# ArcadeMachine.net
KiCad netlist of a schematic drawn in EAGLE
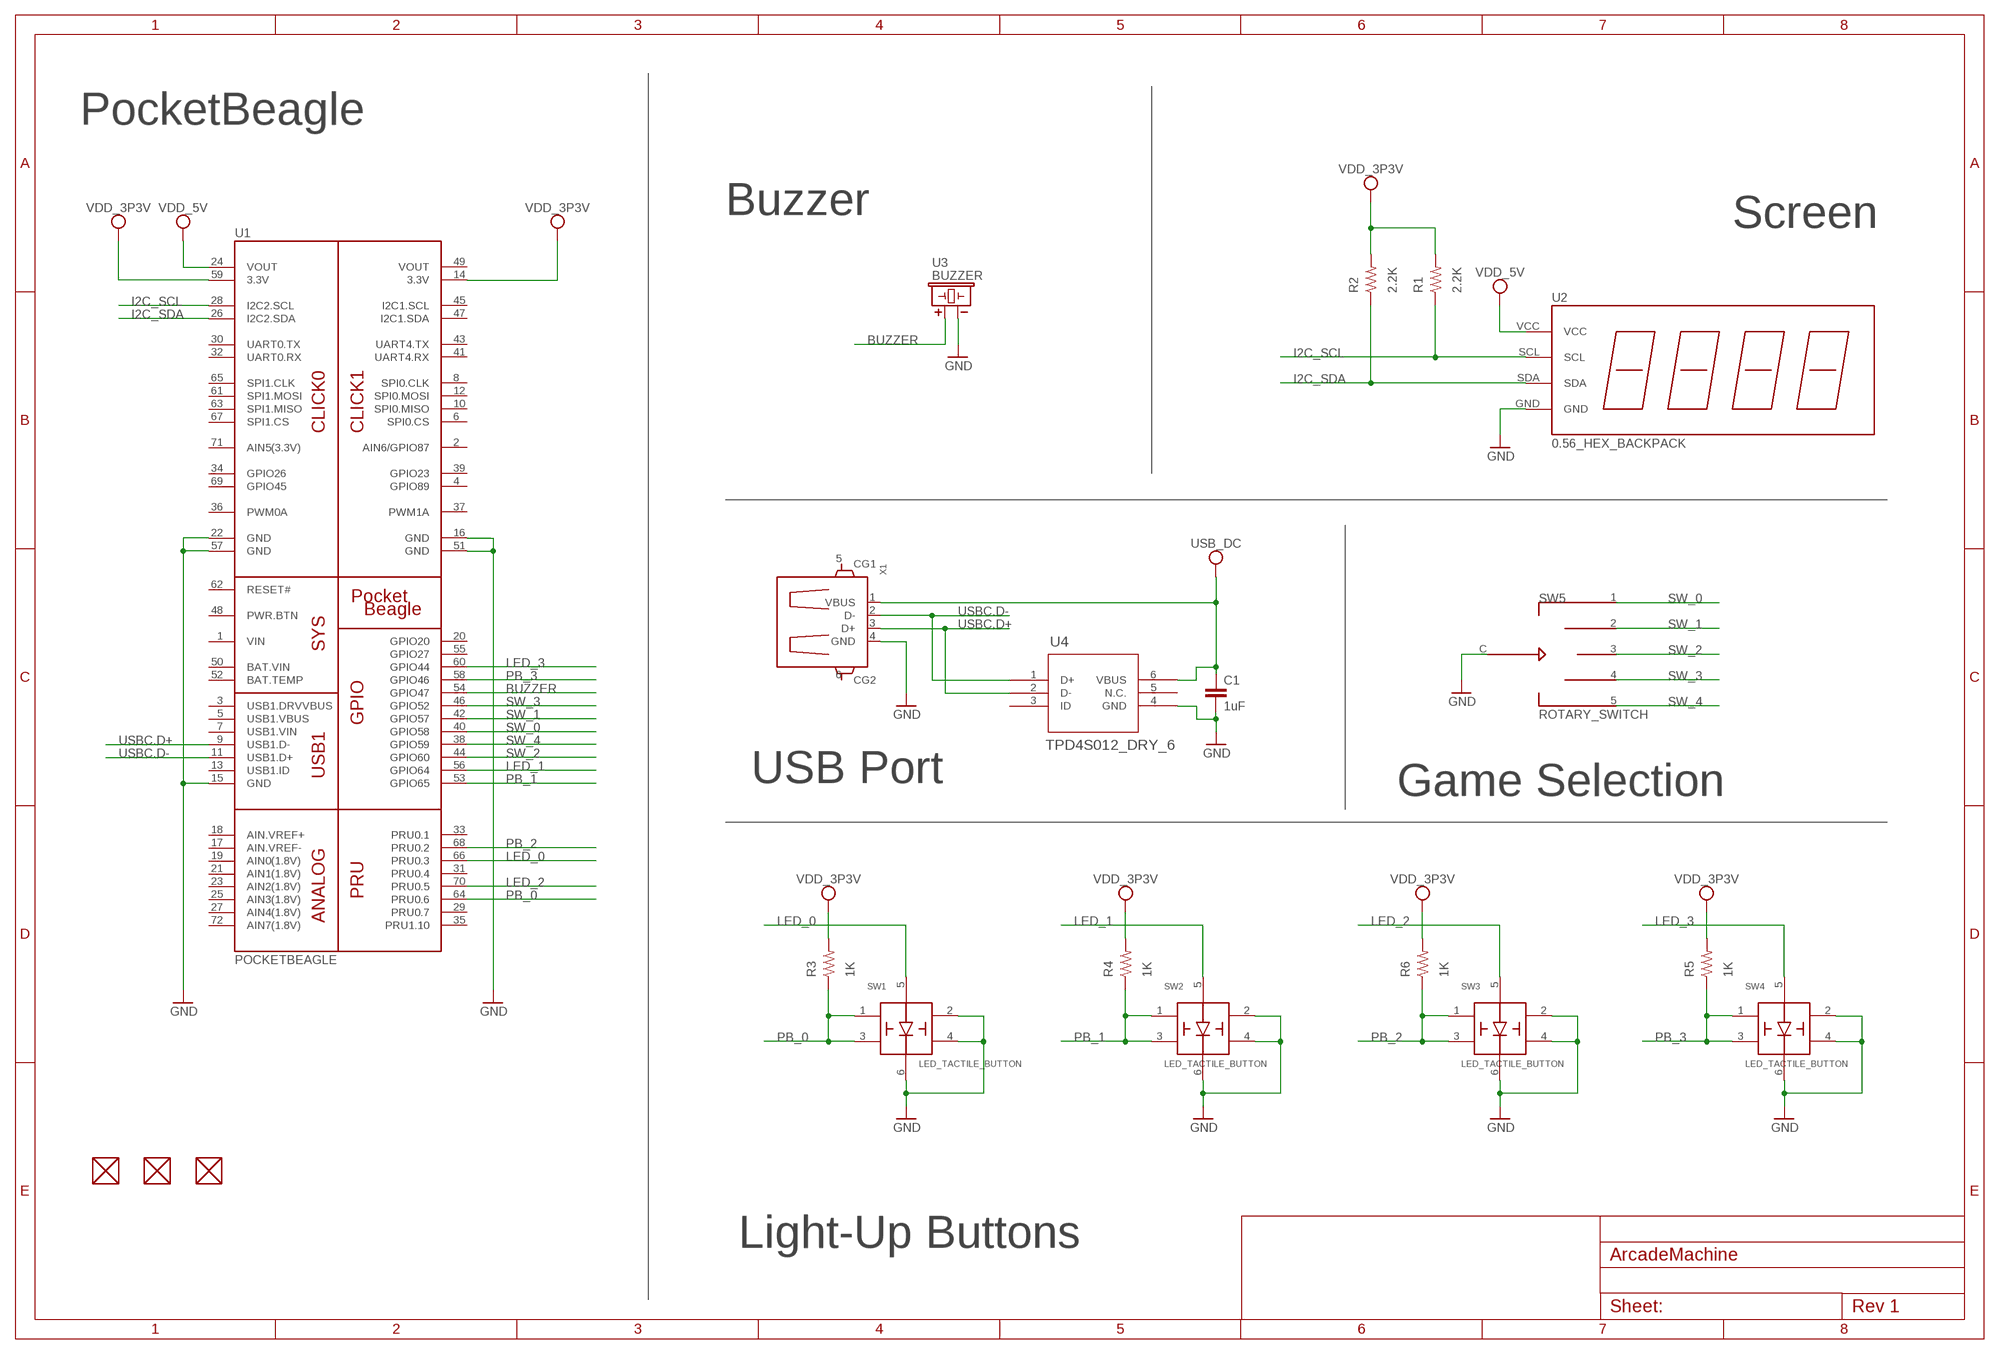
[diagram p0: schematic, sheet 1]

(export (version "E")
  (design (tool "Eeschema 10.0.6"))
  (components
    (comp (ref "C1")
      (value "1uF")
      (footprint "eagle-import:SPARKFUN-CAPACITORS_0603-CAP")
      (libsource (lib "eagle-import") (part "SPARKFUN-CAPACITORS_CAP0603-CAP"))
    )
    (comp (ref "FUD1")
      (value "FIDUCIAL")
      (footprint "eagle-import:FIDUCIAL_40MIL")
      (libsource (lib "eagle-import") (part "FIDUCIAL"))
    )
    (comp (ref "FUD2")
      (value "FIDUCIAL")
      (footprint "eagle-import:FIDUCIAL_40MIL")
      (libsource (lib "eagle-import") (part "FIDUCIAL"))
    )
    (comp (ref "FUD3")
      (value "FIDUCIAL")
      (footprint "eagle-import:FIDUCIAL_40MIL")
      (libsource (lib "eagle-import") (part "FIDUCIAL"))
    )
    (comp (ref "R1")
      (value "2.2K")
      (footprint "eagle-import:R0603")
      (libsource (lib "eagle-import") (part "ENGI301_R_R0603"))
    )
    (comp (ref "R2")
      (value "2.2K")
      (footprint "eagle-import:R0603")
      (libsource (lib "eagle-import") (part "ENGI301_R_R0603"))
    )
    (comp (ref "R3")
      (value "1K")
      (footprint "eagle-import:R0603")
      (libsource (lib "eagle-import") (part "R_R0603"))
    )
    (comp (ref "R4")
      (value "1K")
      (footprint "eagle-import:R0603")
      (libsource (lib "eagle-import") (part "R_R0603"))
    )
    (comp (ref "R5")
      (value "1K")
      (footprint "eagle-import:R0603")
      (libsource (lib "eagle-import") (part "R_R0603"))
    )
    (comp (ref "R6")
      (value "1K")
      (footprint "eagle-import:R0603")
      (libsource (lib "eagle-import") (part "R_R0603"))
    )
    (comp (ref "SW1")
      (value "LED_TACTILE_BUTTON")
      (footprint "eagle-import:LED_TACTILE_BUTTON")
      (libsource (lib "eagle-import") (part "LED_TACTILE_BUTTON"))
    )
    (comp (ref "SW2")
      (value "LED_TACTILE_BUTTON")
      (footprint "eagle-import:LED_TACTILE_BUTTON")
      (libsource (lib "eagle-import") (part "LED_TACTILE_BUTTON"))
    )
    (comp (ref "SW3")
      (value "LED_TACTILE_BUTTON")
      (footprint "eagle-import:LED_TACTILE_BUTTON")
      (libsource (lib "eagle-import") (part "LED_TACTILE_BUTTON"))
    )
    (comp (ref "SW4")
      (value "LED_TACTILE_BUTTON")
      (footprint "eagle-import:LED_TACTILE_BUTTON")
      (libsource (lib "eagle-import") (part "LED_TACTILE_BUTTON"))
    )
    (comp (ref "SW5")
      (value "ROTARY_SWITCH")
      (footprint "eagle-import:ROTARY_SWITCH")
      (libsource (lib "eagle-import") (part "ROTARY_SWITCH"))
    )
    (comp (ref "U1")
      (value "POCKETBEAGLE")
      (footprint "eagle-import:POCKETBEAGLE")
      (libsource (lib "eagle-import") (part "POCKETBEAGLE"))
    )
    (comp (ref "U2")
      (value "0.56_HEX_BACKPACK")
      (footprint "eagle-import:0.56_HEX_BACKPACK")
      (libsource (lib "eagle-import") (part "0.56_HEX_BACKPACK"))
    )
    (comp (ref "U3")
      (value "BUZZER")
      (footprint "eagle-import:BUZZER_6.5MM")
      (libsource (lib "eagle-import") (part "BUZZER"))
    )
    (comp (ref "U4")
      (value "TPD4S012_DRY_6")
      (footprint "eagle-import:BEAGLEBONE_BLUE_DRY6")
      (fields
        (field (name "GENERIC_PART_NUMBER") "TPD4S012")
        (field (name "MANUFACTURER") "Texas Instruments")
        (field (name "MANUFACTURER_PART_NUMBER") "tpd4s012_dry_6")
      )
      (libsource (lib "eagle-import") (part "TPD4S012_DRY_6"))
    )
    (comp (ref "X1")
      (value "GHI2_USB_HOST_W/CHASSIS_GND")
      (footprint "eagle-import:GHI2_USB_HOST_HORIZONTAL_W_CHASSIS_GND")
      (libsource (lib "eagle-import") (part "GHI2_USB_HOST_W/CHASSIS_GND"))
    )
  )
  (nets
    (net (code "1") (name "/BAT.VIN") (class "Default")
      (node (ref "U1") (pin "50") (pinfunction "BAT.VIN_50") (pintype "power_in"))
    )
    (net (code "2") (name "/BUZZER") (class "Default")
      (node (ref "U1") (pin "54") (pinfunction "GPIO47_54") (pintype "bidirectional"))
      (node (ref "U3") (pin "+") (pinfunction "+_+") (pintype "passive"))
    )
    (net (code "3") (name "/I2C_SCL") (class "Default")
      (node (ref "R1") (pin "1") (pinfunction "1_1") (pintype "passive"))
      (node (ref "U1") (pin "28") (pinfunction "I2C2.SCL_28") (pintype "bidirectional"))
      (node (ref "U2") (pin "SCL") (pinfunction "SCL_SCL") (pintype "bidirectional"))
    )
    (net (code "4") (name "/I2C_SDA") (class "Default")
      (node (ref "R2") (pin "1") (pinfunction "1_1") (pintype "passive"))
      (node (ref "U1") (pin "26") (pinfunction "I2C2.SDA_26") (pintype "bidirectional"))
      (node (ref "U2") (pin "SDA") (pinfunction "SDA_SDA") (pintype "bidirectional"))
    )
    (net (code "5") (name "/LED_0") (class "Default")
      (node (ref "SW1") (pin "5") (pinfunction "5_5") (pintype "bidirectional"))
      (node (ref "U1") (pin "66") (pinfunction "PRU0.3_66") (pintype "bidirectional"))
    )
    (net (code "6") (name "/LED_1") (class "Default")
      (node (ref "SW2") (pin "5") (pinfunction "5_5") (pintype "bidirectional"))
      (node (ref "U1") (pin "56") (pinfunction "GPIO64_56") (pintype "bidirectional"))
    )
    (net (code "7") (name "/LED_2") (class "Default")
      (node (ref "SW3") (pin "5") (pinfunction "5_5") (pintype "bidirectional"))
      (node (ref "U1") (pin "70") (pinfunction "PRU0.5_70") (pintype "bidirectional"))
    )
    (net (code "8") (name "/LED_3") (class "Default")
      (node (ref "SW4") (pin "5") (pinfunction "5_5") (pintype "bidirectional"))
      (node (ref "U1") (pin "60") (pinfunction "GPIO44_60") (pintype "bidirectional"))
    )
    (net (code "9") (name "/PB_0") (class "Default")
      (node (ref "R3") (pin "1") (pinfunction "1_1") (pintype "passive"))
      (node (ref "SW1") (pin "1") (pinfunction "1_1") (pintype "bidirectional"))
      (node (ref "SW1") (pin "3") (pinfunction "3_3") (pintype "bidirectional"))
      (node (ref "U1") (pin "64") (pinfunction "PRU0.6_64") (pintype "bidirectional"))
    )
    (net (code "10") (name "/PB_1") (class "Default")
      (node (ref "R4") (pin "1") (pinfunction "1_1") (pintype "passive"))
      (node (ref "SW2") (pin "1") (pinfunction "1_1") (pintype "bidirectional"))
      (node (ref "SW2") (pin "3") (pinfunction "3_3") (pintype "bidirectional"))
      (node (ref "U1") (pin "53") (pinfunction "GPIO65_53") (pintype "bidirectional"))
    )
    (net (code "11") (name "/PB_2") (class "Default")
      (node (ref "R6") (pin "1") (pinfunction "1_1") (pintype "passive"))
      (node (ref "SW3") (pin "1") (pinfunction "1_1") (pintype "bidirectional"))
      (node (ref "SW3") (pin "3") (pinfunction "3_3") (pintype "bidirectional"))
      (node (ref "U1") (pin "68") (pinfunction "PRU0.2_68") (pintype "bidirectional"))
    )
    (net (code "12") (name "/PB_3") (class "Default")
      (node (ref "R5") (pin "1") (pinfunction "1_1") (pintype "passive"))
      (node (ref "SW4") (pin "1") (pinfunction "1_1") (pintype "bidirectional"))
      (node (ref "SW4") (pin "3") (pinfunction "3_3") (pintype "bidirectional"))
      (node (ref "U1") (pin "58") (pinfunction "GPIO46_58") (pintype "bidirectional"))
    )
    (net (code "13") (name "/SW_0") (class "Default")
      (node (ref "SW5") (pin "1") (pinfunction "1_1") (pintype "bidirectional"))
      (node (ref "U1") (pin "40") (pinfunction "GPIO58_40") (pintype "bidirectional"))
    )
    (net (code "14") (name "/SW_1") (class "Default")
      (node (ref "SW5") (pin "2") (pinfunction "2_2") (pintype "bidirectional"))
      (node (ref "U1") (pin "42") (pinfunction "GPIO57_42") (pintype "bidirectional"))
    )
    (net (code "15") (name "/SW_2") (class "Default")
      (node (ref "SW5") (pin "3") (pinfunction "3_3") (pintype "bidirectional"))
      (node (ref "U1") (pin "44") (pinfunction "GPIO60_44") (pintype "bidirectional"))
    )
    (net (code "16") (name "/SW_3") (class "Default")
      (node (ref "SW5") (pin "4") (pinfunction "4_4") (pintype "bidirectional"))
      (node (ref "U1") (pin "46") (pinfunction "GPIO52_46") (pintype "bidirectional"))
    )
    (net (code "17") (name "/SW_4") (class "Default")
      (node (ref "SW5") (pin "5") (pinfunction "5_5") (pintype "bidirectional"))
      (node (ref "U1") (pin "38") (pinfunction "GPIO59_38") (pintype "bidirectional"))
    )
    (net (code "18") (name "/USBC.D+") (class "Default")
      (node (ref "U1") (pin "9") (pinfunction "USB1.D-_9") (pintype "bidirectional"))
      (node (ref "U4") (pin "2") (pinfunction "D-_2") (pintype "passive"))
      (node (ref "X1") (pin "3") (pinfunction "D+_3") (pintype "bidirectional"))
    )
    (net (code "19") (name "/USBC.D-") (class "Default")
      (node (ref "U1") (pin "11") (pinfunction "USB1.D+_11") (pintype "bidirectional"))
      (node (ref "U4") (pin "1") (pinfunction "D+_1") (pintype "passive"))
      (node (ref "X1") (pin "2") (pinfunction "D-_2") (pintype "bidirectional"))
    )
    (net (code "20") (name "/VIN") (class "Default")
      (node (ref "U1") (pin "1") (pinfunction "VIN_1") (pintype "power_in"))
    )
    (net (code "21") (name "/VOUT") (class "Default")
      (node (ref "U1") (pin "49") (pinfunction "VOUT_49") (pintype "power_in"))
    )
    (net (code "22") (name "GND") (class "Default")
      (node (ref "C1") (pin "2") (pinfunction "2_2") (pintype "passive"))
      (node (ref "SW1") (pin "2") (pinfunction "2_2") (pintype "bidirectional"))
      (node (ref "SW1") (pin "4") (pinfunction "4_4") (pintype "bidirectional"))
      (node (ref "SW1") (pin "6") (pinfunction "6_6") (pintype "bidirectional"))
      (node (ref "SW2") (pin "2") (pinfunction "2_2") (pintype "bidirectional"))
      (node (ref "SW2") (pin "4") (pinfunction "4_4") (pintype "bidirectional"))
      (node (ref "SW2") (pin "6") (pinfunction "6_6") (pintype "bidirectional"))
      (node (ref "SW3") (pin "2") (pinfunction "2_2") (pintype "bidirectional"))
      (node (ref "SW3") (pin "4") (pinfunction "4_4") (pintype "bidirectional"))
      (node (ref "SW3") (pin "6") (pinfunction "6_6") (pintype "bidirectional"))
      (node (ref "SW4") (pin "2") (pinfunction "2_2") (pintype "bidirectional"))
      (node (ref "SW4") (pin "4") (pinfunction "4_4") (pintype "bidirectional"))
      (node (ref "SW4") (pin "6") (pinfunction "6_6") (pintype "bidirectional"))
      (node (ref "SW5") (pin "C") (pinfunction "C_C") (pintype "bidirectional"))
      (node (ref "U1") (pin "15") (pinfunction "GND_15") (pintype "bidirectional"))
      (node (ref "U1") (pin "16") (pinfunction "GND_16") (pintype "power_in"))
      (node (ref "U1") (pin "22") (pinfunction "GND_22") (pintype "power_in"))
      (node (ref "U1") (pin "51") (pinfunction "GND_51") (pintype "power_in"))
      (node (ref "U1") (pin "57") (pinfunction "GND_57") (pintype "power_in"))
      (node (ref "U2") (pin "GND") (pinfunction "GND_GND") (pintype "bidirectional"))
      (node (ref "U3") (pin "-") (pinfunction "-_-") (pintype "passive"))
      (node (ref "U4") (pin "4") (pinfunction "GND_4") (pintype "power_in"))
      (node (ref "X1") (pin "4") (pinfunction "GND_4") (pintype "bidirectional"))
    )
    (net (code "23") (name "USB_DC") (class "Default")
      (node (ref "C1") (pin "1") (pinfunction "1_1") (pintype "passive"))
      (node (ref "U4") (pin "6") (pinfunction "VBUS_6") (pintype "passive"))
      (node (ref "X1") (pin "1") (pinfunction "VBUS_1") (pintype "bidirectional"))
    )
    (net (code "24") (name "VDD_3P3V") (class "Default")
      (node (ref "R1") (pin "2") (pinfunction "2_2") (pintype "passive"))
      (node (ref "R2") (pin "2") (pinfunction "2_2") (pintype "passive"))
      (node (ref "R3") (pin "2") (pinfunction "2_2") (pintype "passive"))
      (node (ref "R4") (pin "2") (pinfunction "2_2") (pintype "passive"))
      (node (ref "R5") (pin "2") (pinfunction "2_2") (pintype "passive"))
      (node (ref "R6") (pin "2") (pinfunction "2_2") (pintype "passive"))
      (node (ref "U1") (pin "14") (pinfunction "3.3V_14") (pintype "power_in"))
      (node (ref "U1") (pin "59") (pinfunction "3.3V_59") (pintype "power_in"))
    )
    (net (code "25") (name "VDD_5V") (class "Default")
      (node (ref "U1") (pin "24") (pinfunction "VOUT_24") (pintype "power_in"))
      (node (ref "U2") (pin "VCC") (pinfunction "VCC_VCC") (pintype "power_in"))
    )
    (net (code "26") (name "unconnected-(FUD1-PadP$1)") (class "Default")
      (node (ref "FUD1") (pin "P$1") (pinfunction "P$1_P$1") (pintype "no_connect"))
    )
    (net (code "27") (name "unconnected-(FUD2-PadP$1)") (class "Default")
      (node (ref "FUD2") (pin "P$1") (pinfunction "P$1_P$1") (pintype "no_connect"))
    )
    (net (code "28") (name "unconnected-(FUD3-PadP$1)") (class "Default")
      (node (ref "FUD3") (pin "P$1") (pinfunction "P$1_P$1") (pintype "no_connect"))
    )
    (net (code "29") (name "unconnected-(U1-AIN.VREF+-Pad18)") (class "Default")
      (node (ref "U1") (pin "18") (pinfunction "AIN.VREF+_18") (pintype "input"))
    )
    (net (code "30") (name "unconnected-(U1-AIN.VREF--Pad17)") (class "Default")
      (node (ref "U1") (pin "17") (pinfunction "AIN.VREF-_17") (pintype "input"))
    )
    (net (code "31") (name "unconnected-(U1-AIN0(1.8V)-Pad19)") (class "Default")
      (node (ref "U1") (pin "19") (pinfunction "AIN0(1.8V)_19") (pintype "input"))
    )
    (net (code "32") (name "unconnected-(U1-AIN1(1.8V)-Pad21)") (class "Default")
      (node (ref "U1") (pin "21") (pinfunction "AIN1(1.8V)_21") (pintype "input"))
    )
    (net (code "33") (name "unconnected-(U1-AIN2(1.8V)-Pad23)") (class "Default")
      (node (ref "U1") (pin "23") (pinfunction "AIN2(1.8V)_23") (pintype "input"))
    )
    (net (code "34") (name "unconnected-(U1-AIN3(1.8V)-Pad25)") (class "Default")
      (node (ref "U1") (pin "25") (pinfunction "AIN3(1.8V)_25") (pintype "input"))
    )
    (net (code "35") (name "unconnected-(U1-AIN4(1.8V)-Pad27)") (class "Default")
      (node (ref "U1") (pin "27") (pinfunction "AIN4(1.8V)_27") (pintype "input"))
    )
    (net (code "36") (name "unconnected-(U1-AIN5(3.3V)-Pad71)") (class "Default")
      (node (ref "U1") (pin "71") (pinfunction "AIN5(3.3V)_71") (pintype "bidirectional"))
    )
    (net (code "37") (name "unconnected-(U1-AIN6{slash}GPIO87-Pad2)") (class "Default")
      (node (ref "U1") (pin "2") (pinfunction "AIN6/GPIO87_2") (pintype "bidirectional"))
    )
    (net (code "38") (name "unconnected-(U1-AIN7(1.8V)-Pad72)") (class "Default")
      (node (ref "U1") (pin "72") (pinfunction "AIN7(1.8V)_72") (pintype "input"))
    )
    (net (code "39") (name "unconnected-(U1-BAT.TEMP-Pad52)") (class "Default")
      (node (ref "U1") (pin "52") (pinfunction "BAT.TEMP_52") (pintype "input"))
    )
    (net (code "40") (name "unconnected-(U1-GPIO20-Pad20)") (class "Default")
      (node (ref "U1") (pin "20") (pinfunction "GPIO20_20") (pintype "bidirectional"))
    )
    (net (code "41") (name "unconnected-(U1-GPIO23-Pad39)") (class "Default")
      (node (ref "U1") (pin "39") (pinfunction "GPIO23_39") (pintype "bidirectional"))
    )
    (net (code "42") (name "unconnected-(U1-GPIO26-Pad34)") (class "Default")
      (node (ref "U1") (pin "34") (pinfunction "GPIO26_34") (pintype "bidirectional"))
    )
    (net (code "43") (name "unconnected-(U1-GPIO27-Pad55)") (class "Default")
      (node (ref "U1") (pin "55") (pinfunction "GPIO27_55") (pintype "bidirectional"))
    )
    (net (code "44") (name "unconnected-(U1-GPIO45-Pad69)") (class "Default")
      (node (ref "U1") (pin "69") (pinfunction "GPIO45_69") (pintype "bidirectional"))
    )
    (net (code "45") (name "unconnected-(U1-GPIO89-Pad4)") (class "Default")
      (node (ref "U1") (pin "4") (pinfunction "GPIO89_4") (pintype "bidirectional"))
    )
    (net (code "46") (name "unconnected-(U1-I2C1.SCL-Pad45)") (class "Default")
      (node (ref "U1") (pin "45") (pinfunction "I2C1.SCL_45") (pintype "bidirectional"))
    )
    (net (code "47") (name "unconnected-(U1-I2C1.SDA-Pad47)") (class "Default")
      (node (ref "U1") (pin "47") (pinfunction "I2C1.SDA_47") (pintype "bidirectional"))
    )
    (net (code "48") (name "unconnected-(U1-PRU0.1-Pad33)") (class "Default")
      (node (ref "U1") (pin "33") (pinfunction "PRU0.1_33") (pintype "bidirectional"))
    )
    (net (code "49") (name "unconnected-(U1-PRU0.4-Pad31)") (class "Default")
      (node (ref "U1") (pin "31") (pinfunction "PRU0.4_31") (pintype "bidirectional"))
    )
    (net (code "50") (name "unconnected-(U1-PRU0.7-Pad29)") (class "Default")
      (node (ref "U1") (pin "29") (pinfunction "PRU0.7_29") (pintype "bidirectional"))
    )
    (net (code "51") (name "unconnected-(U1-PRU1.10-Pad35)") (class "Default")
      (node (ref "U1") (pin "35") (pinfunction "PRU1.10_35") (pintype "bidirectional"))
    )
    (net (code "52") (name "unconnected-(U1-PWM0A-Pad36)") (class "Default")
      (node (ref "U1") (pin "36") (pinfunction "PWM0A_36") (pintype "bidirectional"))
    )
    (net (code "53") (name "unconnected-(U1-PWM1A-Pad37)") (class "Default")
      (node (ref "U1") (pin "37") (pinfunction "PWM1A_37") (pintype "bidirectional"))
    )
    (net (code "54") (name "unconnected-(U1-PWR.BTN-Pad48)") (class "Default")
      (node (ref "U1") (pin "48") (pinfunction "PWR.BTN_48") (pintype "input"))
    )
    (net (code "55") (name "unconnected-(U1-RESET#-Pad62)") (class "Default")
      (node (ref "U1") (pin "62") (pinfunction "RESET#_62") (pintype "input"))
    )
    (net (code "56") (name "unconnected-(U1-SPI0.CLK-Pad8)") (class "Default")
      (node (ref "U1") (pin "8") (pinfunction "SPI0.CLK_8") (pintype "bidirectional"))
    )
    (net (code "57") (name "unconnected-(U1-SPI0.CS-Pad6)") (class "Default")
      (node (ref "U1") (pin "6") (pinfunction "SPI0.CS_6") (pintype "bidirectional"))
    )
    (net (code "58") (name "unconnected-(U1-SPI0.MISO-Pad10)") (class "Default")
      (node (ref "U1") (pin "10") (pinfunction "SPI0.MISO_10") (pintype "bidirectional"))
    )
    (net (code "59") (name "unconnected-(U1-SPI0.MOSI-Pad12)") (class "Default")
      (node (ref "U1") (pin "12") (pinfunction "SPI0.MOSI_12") (pintype "bidirectional"))
    )
    (net (code "60") (name "unconnected-(U1-SPI1.CLK-Pad65)") (class "Default")
      (node (ref "U1") (pin "65") (pinfunction "SPI1.CLK_65") (pintype "bidirectional"))
    )
    (net (code "61") (name "unconnected-(U1-SPI1.CS-Pad67)") (class "Default")
      (node (ref "U1") (pin "67") (pinfunction "SPI1.CS_67") (pintype "bidirectional"))
    )
    (net (code "62") (name "unconnected-(U1-SPI1.MISO-Pad63)") (class "Default")
      (node (ref "U1") (pin "63") (pinfunction "SPI1.MISO_63") (pintype "bidirectional"))
    )
    (net (code "63") (name "unconnected-(U1-SPI1.MOSI-Pad61)") (class "Default")
      (node (ref "U1") (pin "61") (pinfunction "SPI1.MOSI_61") (pintype "bidirectional"))
    )
    (net (code "64") (name "unconnected-(U1-UART0.RX-Pad32)") (class "Default")
      (node (ref "U1") (pin "32") (pinfunction "UART0.RX_32") (pintype "bidirectional"))
    )
    (net (code "65") (name "unconnected-(U1-UART0.TX-Pad30)") (class "Default")
      (node (ref "U1") (pin "30") (pinfunction "UART0.TX_30") (pintype "bidirectional"))
    )
    (net (code "66") (name "unconnected-(U1-UART4.RX-Pad41)") (class "Default")
      (node (ref "U1") (pin "41") (pinfunction "UART4.RX_41") (pintype "bidirectional"))
    )
    (net (code "67") (name "unconnected-(U1-UART4.TX-Pad43)") (class "Default")
      (node (ref "U1") (pin "43") (pinfunction "UART4.TX_43") (pintype "bidirectional"))
    )
    (net (code "68") (name "unconnected-(U1-USB1.DRVVBUS-Pad3)") (class "Default")
      (node (ref "U1") (pin "3") (pinfunction "USB1.DRVVBUS_3") (pintype "bidirectional"))
    )
    (net (code "69") (name "unconnected-(U1-USB1.ID-Pad13)") (class "Default")
      (node (ref "U1") (pin "13") (pinfunction "USB1.ID_13") (pintype "bidirectional"))
    )
    (net (code "70") (name "unconnected-(U1-USB1.VBUS-Pad5)") (class "Default")
      (node (ref "U1") (pin "5") (pinfunction "USB1.VBUS_5") (pintype "bidirectional"))
    )
    (net (code "71") (name "unconnected-(U1-USB1.VIN-Pad7)") (class "Default")
      (node (ref "U1") (pin "7") (pinfunction "USB1.VIN_7") (pintype "bidirectional"))
    )
    (net (code "72") (name "unconnected-(U4-ID-Pad3)") (class "Default")
      (node (ref "U4") (pin "3") (pinfunction "ID_3") (pintype "passive"))
    )
    (net (code "73") (name "unconnected-(U4-N.C.-Pad5)") (class "Default")
      (node (ref "U4") (pin "5") (pinfunction "N.C._5") (pintype "no_connect"))
    )
    (net (code "74") (name "unconnected-(X1-CG1-Pad5)") (class "Default")
      (node (ref "X1") (pin "5") (pinfunction "CG1_5") (pintype "bidirectional"))
    )
    (net (code "75") (name "unconnected-(X1-CG2-Pad6)") (class "Default")
      (node (ref "X1") (pin "6") (pinfunction "CG2_6") (pintype "bidirectional"))
    )
  )
)
